# AFE_BQ-Chip.net
KiCad netlist of a schematic drawn in Altium Designer
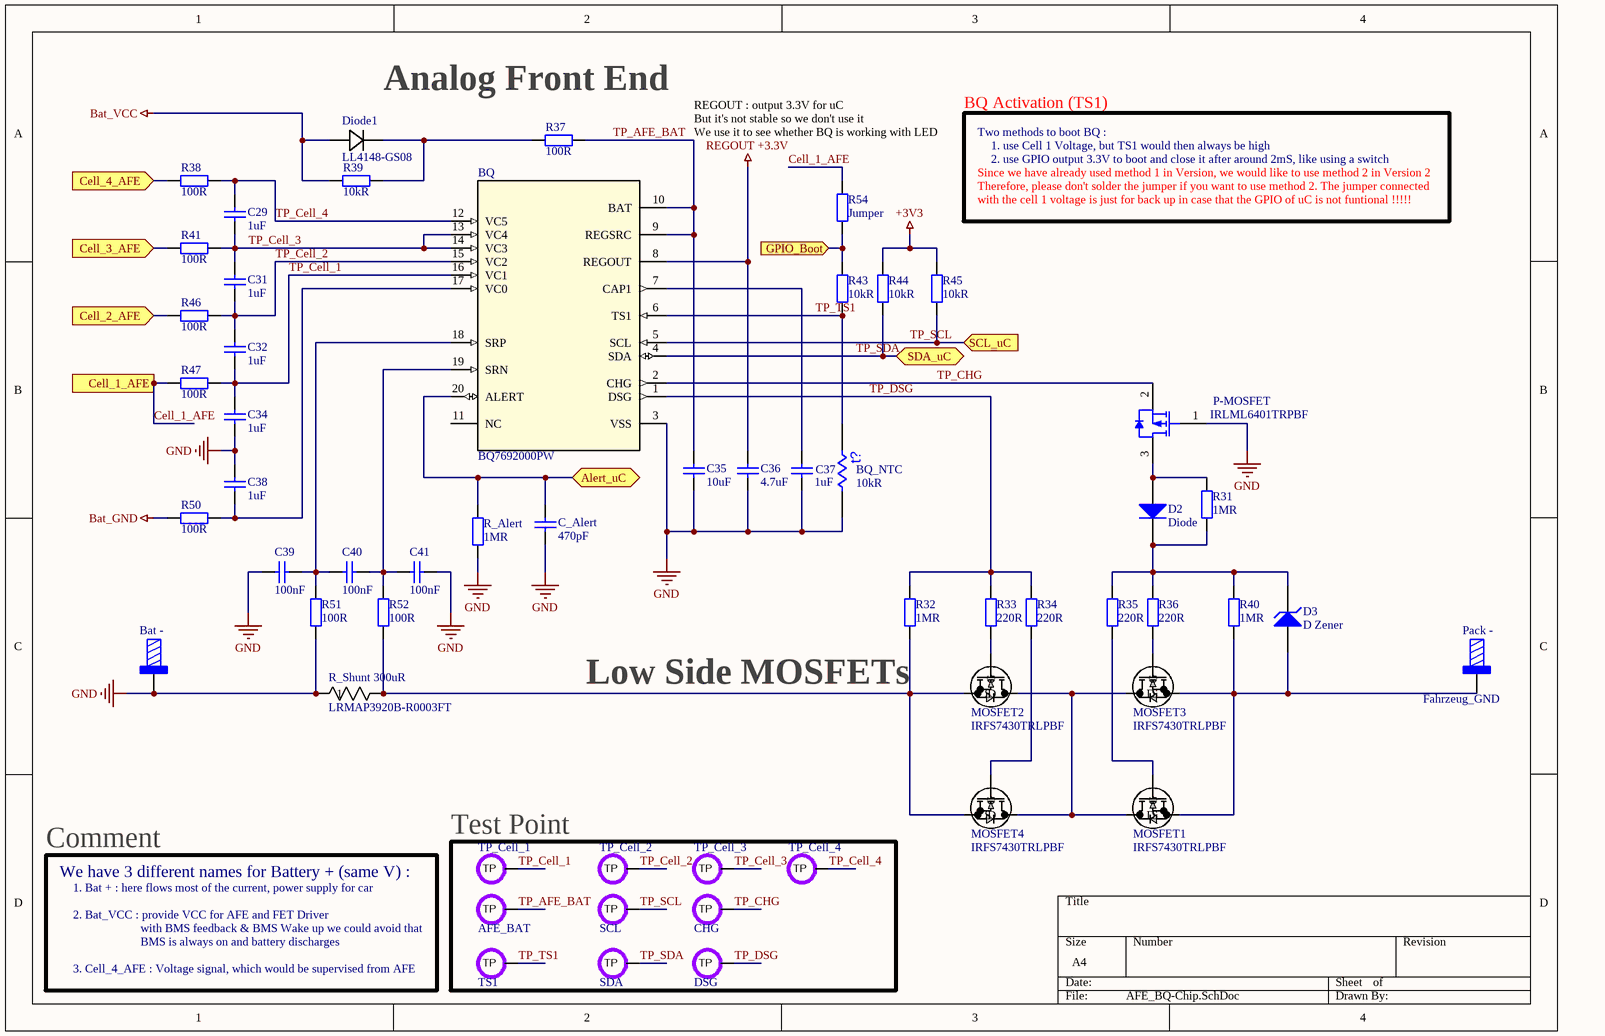
[diagram p0: AFE_BQ-Chip.SchDoc]

(export (version "E")
  (design (tool "Eeschema 10.0.6"))
  (components
    (comp (ref "AFE_BAT")
      (value "TP_1")
      (footprint "Test point")
      (libsource (lib "Schlib1") (part "Test point"))
    )
    (comp (ref "Bat -")
      (value "M4x6mm")
      (footprint "7461096_for chemical surfaces")
      (description "WP-SHFU Press-Fit with External thread, full plain, 7x7mm, 9 pins, M4x6mm, 130A")
      (fields (field (name "PART NUMBER") "7461096") (field (name "PUBLISHER") "Wurth Elektronik"))
      (libsource (lib "GND Pillar") (part "7461096"))
    )
    (comp (ref "BQ")
      (value "BQ7692000PW")
      (footprint "PW0020A_N")
      (description "AFE Cell battery monitor")
      (fields
        (field (name "PARTNUMBER") "BQ7692000PWR")
        (field (name "MANUFACTURER") "Texas Instruments")
        (field (name "COPYRIGHT") "Copyright (C) 2018 Accelerated Designs. All rights reserved")
      )
      (libsource (lib "BQ7692000PW") (part "BQ7692000PW"))
    )
    (comp (ref "BQ_NTC")
      (value "10kR")
      (footprint "J1-0603")
      (description "Thermistor")
      (fields (field (name "PUBLISHER") "Altium Limited"))
      (libsource (lib "Miscellaneous Devices") (part "Res Thermal"))
    )
    (comp (ref "C29")
      (value "1uF")
      (footprint "1608[0603]")
      (description "Capacitor")
      (fields (field (name "PUBLISHER") "Altium Limited"))
      (libsource (lib "Miscellaneous Devices") (part "Cap"))
    )
    (comp (ref "C31")
      (value "1uF")
      (footprint "1608[0603]")
      (description "Capacitor")
      (fields (field (name "PUBLISHER") "Altium Limited"))
      (libsource (lib "Miscellaneous Devices") (part "Cap"))
    )
    (comp (ref "C32")
      (value "1uF")
      (footprint "1608[0603]")
      (description "Capacitor")
      (fields (field (name "PUBLISHER") "Altium Limited"))
      (libsource (lib "Miscellaneous Devices") (part "Cap"))
    )
    (comp (ref "C34")
      (value "1uF")
      (footprint "1608[0603]")
      (description "Capacitor")
      (fields (field (name "PUBLISHER") "Altium Limited"))
      (libsource (lib "Miscellaneous Devices") (part "Cap"))
    )
    (comp (ref "C35")
      (value "10uF")
      (footprint "1608[0603]")
      (description "Capacitor")
      (fields (field (name "PUBLISHER") "Altium Limited"))
      (libsource (lib "Miscellaneous Devices") (part "Cap"))
    )
    (comp (ref "C36")
      (value "4.7uF")
      (footprint "1608[0603]")
      (description "Capacitor")
      (fields (field (name "PUBLISHER") "Altium Limited"))
      (libsource (lib "Miscellaneous Devices") (part "Cap"))
    )
    (comp (ref "C37")
      (value "1uF")
      (footprint "1608[0603]")
      (description "Capacitor")
      (fields (field (name "PUBLISHER") "Altium Limited"))
      (libsource (lib "Miscellaneous Devices") (part "Cap"))
    )
    (comp (ref "C38")
      (value "1uF")
      (footprint "1608[0603]")
      (description "Capacitor")
      (fields (field (name "PUBLISHER") "Altium Limited"))
      (libsource (lib "Miscellaneous Devices") (part "Cap"))
    )
    (comp (ref "C39")
      (value "100nF")
      (footprint "1608[0603]")
      (description "Capacitor")
      (fields (field (name "PUBLISHER") "Altium Limited"))
      (libsource (lib "Miscellaneous Devices") (part "Cap"))
    )
    (comp (ref "C40")
      (value "100nF")
      (footprint "1608[0603]")
      (description "Capacitor")
      (fields (field (name "PUBLISHER") "Altium Limited"))
      (libsource (lib "Miscellaneous Devices") (part "Cap"))
    )
    (comp (ref "C41")
      (value "100nF")
      (footprint "1608[0603]")
      (description "Capacitor")
      (fields (field (name "PUBLISHER") "Altium Limited"))
      (libsource (lib "Miscellaneous Devices") (part "Cap"))
    )
    (comp (ref "CHG") (value "TP_1") (footprint "Test point") (libsource (lib "Schlib1") (part "Test point")))
    (comp (ref "C_Alert")
      (value "470pF")
      (footprint "1608[0603]")
      (description "Capacitor")
      (fields (field (name "PUBLISHER") "Altium Limited"))
      (libsource (lib "Miscellaneous Devices") (part "Cap"))
    )
    (comp (ref "D2")
      (value "Diode")
      (footprint "SMB")
      (description "Default Diode")
      (fields (field (name "PUBLISHER") "Altium Limited"))
      (libsource (lib "Miscellaneous Devices") (part "Diode"))
    )
    (comp (ref "D3")
      (value "D Zener")
      (footprint "SMB")
      (description "Zener Diode")
      (fields (field (name "PUBLISHER") "Altium Limited"))
      (libsource (lib "Miscellaneous Devices") (part "D Zener"))
    )
    (comp (ref "Diode1")
      (value "LL4148-GS08")
      (footprint "MELF_SOD-80_VIS")
      (description "No Description Available")
      (fields (field (name "COPYRIGHT") "Copyright (C) 2018 Accelerated Designs. All rights reserved"))
      (libsource (lib "Small Signal Switching Diodes") (part "LL4148-GS08"))
    )
    (comp (ref "DSG") (value "TP_1") (footprint "Test point") (libsource (lib "Schlib1") (part "Test point")))
    (comp (ref "MOSFET1")
      (value "IRFS7430TRLPBF")
      (footprint "D2PAK_TO-263AB_INF-M")
      (description "No Description Available")
      (fields (field (name "COPYRIGHT") "Copyright (C) 2018 Accelerated Designs. All rights reserved"))
      (libsource (lib "Power MOSFET") (part "IRFS7430TRLPBF"))
    )
    (comp (ref "MOSFET2")
      (value "IRFS7430TRLPBF")
      (footprint "D2PAK_TO-263AB_INF-M")
      (description "No Description Available")
      (fields (field (name "COPYRIGHT") "Copyright (C) 2018 Accelerated Designs. All rights reserved"))
      (libsource (lib "Power MOSFET") (part "IRFS7430TRLPBF"))
    )
    (comp (ref "MOSFET3")
      (value "IRFS7430TRLPBF")
      (footprint "D2PAK_TO-263AB_INF-M")
      (description "No Description Available")
      (fields (field (name "COPYRIGHT") "Copyright (C) 2018 Accelerated Designs. All rights reserved"))
      (libsource (lib "Power MOSFET") (part "IRFS7430TRLPBF"))
    )
    (comp (ref "MOSFET4")
      (value "IRFS7430TRLPBF")
      (footprint "D2PAK_TO-263AB_INF-M")
      (description "No Description Available")
      (fields (field (name "COPYRIGHT") "Copyright (C) 2018 Accelerated Designs. All rights reserved"))
      (libsource (lib "Power MOSFET") (part "IRFS7430TRLPBF"))
    )
    (comp (ref "P-MOSFET")
      (value "IRLML6401TRPBF")
      (footprint "INTR-SOT-23-3_V")
      (fields (field (name "MANUFACTURER") "International Rectifier"))
      (libsource (lib "Altium Content Vault") (part "PEMOS-GSD-3"))
    )
    (comp (ref "Pack -")
      (value "Fahrzeug_GND")
      (footprint "7461096_for chemical surfaces")
      (description "WP-SHFU Press-Fit with External thread, full plain, 7x7mm, 9 pins, M4x6mm, 130A")
      (fields (field (name "PART NUMBER") "7461096") (field (name "PUBLISHER") "Wurth Elektronik"))
      (libsource (lib "GND Pillar") (part "7461096"))
    )
    (comp (ref "R31")
      (value "1MR")
      (footprint "J1-0603")
      (description "Resistor")
      (fields (field (name "PUBLISHER") "Altium Limited"))
      (libsource (lib "") (part "Res2_1"))
    )
    (comp (ref "R32")
      (value "1MR")
      (footprint "J1-0603")
      (description "Resistor")
      (fields (field (name "PUBLISHER") "Altium Limited"))
      (libsource (lib "") (part "Res2_1"))
    )
    (comp (ref "R33")
      (value "220R")
      (footprint "J1-0603")
      (description "Resistor")
      (fields (field (name "PUBLISHER") "Altium Limited"))
      (libsource (lib "") (part "Res2_1"))
    )
    (comp (ref "R34")
      (value "220R")
      (footprint "J1-0603")
      (description "Resistor")
      (fields (field (name "PUBLISHER") "Altium Limited"))
      (libsource (lib "") (part "Res2_1"))
    )
    (comp (ref "R35")
      (value "220R")
      (footprint "J1-0603")
      (description "Resistor")
      (fields (field (name "PUBLISHER") "Altium Limited"))
      (libsource (lib "") (part "Res2_1"))
    )
    (comp (ref "R36")
      (value "220R")
      (footprint "J1-0603")
      (description "Resistor")
      (fields (field (name "PUBLISHER") "Altium Limited"))
      (libsource (lib "") (part "Res2_1"))
    )
    (comp (ref "R37")
      (value "100R")
      (footprint "J1-0603")
      (description "Resistor")
      (fields (field (name "PUBLISHER") "Altium Limited"))
      (libsource (lib "Miscellaneous Devices") (part "Res2"))
    )
    (comp (ref "R38")
      (value "100R")
      (footprint "J1-0603")
      (description "Resistor")
      (fields (field (name "PUBLISHER") "Altium Limited"))
      (libsource (lib "Miscellaneous Devices") (part "Res2"))
    )
    (comp (ref "R39")
      (value "10kR")
      (footprint "J1-0603")
      (description "Resistor")
      (fields (field (name "PUBLISHER") "Altium Limited"))
      (libsource (lib "Miscellaneous Devices") (part "Res2"))
    )
    (comp (ref "R40")
      (value "1MR")
      (footprint "J1-0603")
      (description "Resistor")
      (fields (field (name "PUBLISHER") "Altium Limited"))
      (libsource (lib "") (part "Res2_1"))
    )
    (comp (ref "R41")
      (value "100R")
      (footprint "J1-0603")
      (description "Resistor")
      (fields (field (name "PUBLISHER") "Altium Limited"))
      (libsource (lib "Miscellaneous Devices") (part "Res2"))
    )
    (comp (ref "R43")
      (value "10kR")
      (footprint "J1-0603")
      (description "Resistor")
      (fields (field (name "PUBLISHER") "Altium Limited"))
      (libsource (lib "Miscellaneous Devices") (part "Res2"))
    )
    (comp (ref "R44")
      (value "10kR")
      (footprint "J1-0603")
      (description "Resistor")
      (fields (field (name "PUBLISHER") "Altium Limited"))
      (libsource (lib "") (part "Res2_1"))
    )
    (comp (ref "R45")
      (value "10kR")
      (footprint "J1-0603")
      (description "Resistor")
      (fields (field (name "PUBLISHER") "Altium Limited"))
      (libsource (lib "") (part "Res2_1"))
    )
    (comp (ref "R46")
      (value "100R")
      (footprint "J1-0603")
      (description "Resistor")
      (fields (field (name "PUBLISHER") "Altium Limited"))
      (libsource (lib "Miscellaneous Devices") (part "Res2"))
    )
    (comp (ref "R47")
      (value "100R")
      (footprint "J1-0603")
      (description "Resistor")
      (fields (field (name "PUBLISHER") "Altium Limited"))
      (libsource (lib "Miscellaneous Devices") (part "Res2"))
    )
    (comp (ref "R50")
      (value "100R")
      (footprint "J1-0603")
      (description "Resistor")
      (fields (field (name "PUBLISHER") "Altium Limited"))
      (libsource (lib "") (part "Res2_1"))
    )
    (comp (ref "R51")
      (value "100R")
      (footprint "J1-0603")
      (description "Resistor")
      (fields (field (name "PUBLISHER") "Altium Limited"))
      (libsource (lib "Miscellaneous Devices") (part "Res2"))
    )
    (comp (ref "R52")
      (value "100R")
      (footprint "J1-0603")
      (description "Resistor")
      (fields (field (name "PUBLISHER") "Altium Limited"))
      (libsource (lib "Miscellaneous Devices") (part "Res2"))
    )
    (comp (ref "R54")
      (value "Jumper")
      (footprint "J1-0603")
      (description "Resistor")
      (fields (field (name "PUBLISHER") "Altium Limited"))
      (libsource (lib "") (part "Res2_2"))
    )
    (comp (ref "R_Alert")
      (value "1MR")
      (footprint "J1-0603")
      (description "Resistor")
      (fields (field (name "PUBLISHER") "Altium Limited"))
      (libsource (lib "Miscellaneous Devices") (part "Res2"))
    )
    (comp (ref "R_Shunt 300uR")
      (value "LRMAP3920B-R0003FT")
      (footprint "RES_LRMAP3920B-R0003FT_WEL")
      (description "No Description Available")
      (fields (field (name "COPYRIGHT") "Copyright (C) 2018 Accelerated Designs. All rights reserved"))
      (libsource (lib "Shunt R") (part "LRMAP3920B-R0003FT"))
    )
    (comp (ref "SCL") (value "TP_1") (footprint "Test point") (libsource (lib "Schlib1") (part "Test point")))
    (comp (ref "SDA") (value "TP_1") (footprint "Test point") (libsource (lib "Schlib1") (part "Test point")))
    (comp (ref "TP_Cell_1")
      (value "TP_1")
      (footprint "Test point")
      (libsource (lib "Schlib1") (part "Test point"))
    )
    (comp (ref "TP_Cell_2")
      (value "TP_1")
      (footprint "Test point")
      (libsource (lib "Schlib1") (part "Test point"))
    )
    (comp (ref "TP_Cell_3")
      (value "TP_1")
      (footprint "Test point")
      (libsource (lib "Schlib1") (part "Test point"))
    )
    (comp (ref "TP_Cell_4")
      (value "TP_1")
      (footprint "Test point")
      (libsource (lib "Schlib1") (part "Test point"))
    )
    (comp (ref "TS1") (value "TP_1") (footprint "Test point") (libsource (lib "Schlib1") (part "Test point")))
  )
  (nets
    (net (code "1") (name "+3V3") (class "Default")
      (node (ref "R44") (pin "1") (pinfunction "1_1") (pintype "passive"))
      (node (ref "R45") (pin "1") (pinfunction "1_1") (pintype "passive"))
    )
    (net (code "2") (name "/Alert_uC") (class "Default")
      (node (ref "BQ") (pin "20") (pinfunction "ALERT_20") (pintype "bidirectional"))
      (node (ref "C_Alert") (pin "1") (pinfunction "1_1") (pintype "passive"))
      (node (ref "R_Alert") (pin "1") (pinfunction "1_1") (pintype "passive"))
    )
    (net (code "3") (name "/Cell_1_AFE") (class "Default")
      (node (ref "R47") (pin "2") (pinfunction "2_2") (pintype "passive"))
      (node (ref "R54") (pin "2") (pinfunction "2_2") (pintype "passive"))
    )
    (net (code "4") (name "/Cell_2_AFE") (class "Default")
      (node (ref "R46") (pin "2") (pinfunction "2_2") (pintype "passive"))
    )
    (net (code "5") (name "/Cell_3_AFE") (class "Default")
      (node (ref "R41") (pin "2") (pinfunction "2_2") (pintype "passive"))
    )
    (net (code "6") (name "/Cell_4_AFE") (class "Default")
      (node (ref "R38") (pin "2") (pinfunction "2_2") (pintype "passive"))
    )
    (net (code "7") (name "/GPIO_Boot") (class "Default")
      (node (ref "R43") (pin "1") (pinfunction "1_1") (pintype "passive"))
      (node (ref "R54") (pin "1") (pinfunction "1_1") (pintype "passive"))
    )
    (net (code "8") (name "/TP_AFE_BAT") (class "Default")
      (node (ref "AFE_BAT") (pin "1") (pinfunction "TP_1") (pintype "passive"))
      (node (ref "BQ") (pin "10") (pinfunction "BAT_10") (pintype "power_in"))
      (node (ref "BQ") (pin "9") (pinfunction "REGSRC_9") (pintype "power_in"))
      (node (ref "C35") (pin "1") (pinfunction "1_1") (pintype "passive"))
      (node (ref "R37") (pin "1") (pinfunction "1_1") (pintype "passive"))
    )
    (net (code "9") (name "/TP_CHG") (class "Default")
      (node (ref "BQ") (pin "2") (pinfunction "CHG_2") (pintype "output"))
      (node (ref "CHG") (pin "1") (pinfunction "TP_1") (pintype "passive"))
      (node (ref "P-MOSFET") (pin "2") (pinfunction "SOURCE_2") (pintype "passive"))
    )
    (net (code "10") (name "/TP_Cell_1") (class "Default")
      (node (ref "BQ") (pin "16") (pinfunction "VC1_16") (pintype "input"))
      (node (ref "C32") (pin "1") (pinfunction "1_1") (pintype "passive"))
      (node (ref "C34") (pin "2") (pinfunction "2_2") (pintype "passive"))
      (node (ref "R47") (pin "1") (pinfunction "1_1") (pintype "passive"))
      (node (ref "TP_Cell_1") (pin "1") (pinfunction "TP_1") (pintype "passive"))
    )
    (net (code "11") (name "/TP_Cell_2") (class "Default")
      (node (ref "BQ") (pin "15") (pinfunction "VC2_15") (pintype "input"))
      (node (ref "C31") (pin "1") (pinfunction "1_1") (pintype "passive"))
      (node (ref "C32") (pin "2") (pinfunction "2_2") (pintype "passive"))
      (node (ref "R46") (pin "1") (pinfunction "1_1") (pintype "passive"))
      (node (ref "TP_Cell_2") (pin "1") (pinfunction "TP_1") (pintype "passive"))
    )
    (net (code "12") (name "/TP_Cell_3") (class "Default")
      (node (ref "BQ") (pin "13") (pinfunction "VC4_13") (pintype "input"))
      (node (ref "BQ") (pin "14") (pinfunction "VC3_14") (pintype "input"))
      (node (ref "C29") (pin "1") (pinfunction "1_1") (pintype "passive"))
      (node (ref "C31") (pin "2") (pinfunction "2_2") (pintype "passive"))
      (node (ref "R41") (pin "1") (pinfunction "1_1") (pintype "passive"))
      (node (ref "TP_Cell_3") (pin "1") (pinfunction "TP_1") (pintype "passive"))
    )
    (net (code "13") (name "/TP_Cell_4") (class "Default")
      (node (ref "BQ") (pin "12") (pinfunction "VC5_12") (pintype "input"))
      (node (ref "C29") (pin "2") (pinfunction "2_2") (pintype "passive"))
      (node (ref "R38") (pin "1") (pinfunction "1_1") (pintype "passive"))
      (node (ref "TP_Cell_4") (pin "1") (pinfunction "TP_1") (pintype "passive"))
    )
    (net (code "14") (name "/TP_DSG") (class "Default")
      (node (ref "BQ") (pin "1") (pinfunction "DSG_1") (pintype "output"))
      (node (ref "DSG") (pin "1") (pinfunction "TP_1") (pintype "passive"))
      (node (ref "R32") (pin "1") (pinfunction "1_1") (pintype "passive"))
      (node (ref "R33") (pin "1") (pinfunction "1_1") (pintype "passive"))
      (node (ref "R34") (pin "1") (pinfunction "1_1") (pintype "passive"))
    )
    (net (code "15") (name "/TP_SCL") (class "Default")
      (node (ref "BQ") (pin "5") (pinfunction "SCL_5") (pintype "input"))
      (node (ref "R45") (pin "2") (pinfunction "2_2") (pintype "passive"))
      (node (ref "SCL") (pin "1") (pinfunction "TP_1") (pintype "passive"))
    )
    (net (code "16") (name "/TP_SDA") (class "Default")
      (node (ref "BQ") (pin "4") (pinfunction "SDA_4") (pintype "bidirectional"))
      (node (ref "R44") (pin "2") (pinfunction "2_2") (pintype "passive"))
      (node (ref "SDA") (pin "1") (pinfunction "TP_1") (pintype "passive"))
    )
    (net (code "17") (name "/TP_TS1") (class "Default")
      (node (ref "BQ") (pin "6") (pinfunction "TS1_6") (pintype "input"))
      (node (ref "BQ_NTC") (pin "1") (pinfunction "1_1") (pintype "passive"))
      (node (ref "R43") (pin "2") (pinfunction "2_2") (pintype "passive"))
      (node (ref "TS1") (pin "1") (pinfunction "TP_1") (pintype "passive"))
    )
    (net (code "18") (name "Bat_GND") (class "Default")
      (node (ref "R50") (pin "2") (pinfunction "2_2") (pintype "passive"))
    )
    (net (code "19") (name "Bat_VCC") (class "Default")
      (node (ref "Diode1") (pin "2") (pinfunction "2_2") (pintype "passive"))
      (node (ref "R39") (pin "2") (pinfunction "2_2") (pintype "passive"))
    )
    (net (code "20") (name "GND") (class "Default")
      (node (ref "BQ") (pin "3") (pinfunction "VSS_3") (pintype "power_in"))
      (node (ref "BQ_NTC") (pin "2") (pinfunction "2_2") (pintype "passive"))
      (node (ref "Bat -") (pin "1") (pinfunction "1_1") (pintype "passive"))
      (node (ref "C34") (pin "1") (pinfunction "1_1") (pintype "passive"))
      (node (ref "C35") (pin "2") (pinfunction "2_2") (pintype "passive"))
      (node (ref "C36") (pin "2") (pinfunction "2_2") (pintype "passive"))
      (node (ref "C37") (pin "2") (pinfunction "2_2") (pintype "passive"))
      (node (ref "C38") (pin "1") (pinfunction "1_1") (pintype "passive"))
      (node (ref "C39") (pin "2") (pinfunction "2_2") (pintype "passive"))
      (node (ref "C41") (pin "1") (pinfunction "1_1") (pintype "passive"))
      (node (ref "C_Alert") (pin "2") (pinfunction "2_2") (pintype "passive"))
      (node (ref "P-MOSFET") (pin "1") (pinfunction "GATE_1") (pintype "passive"))
      (node (ref "R51") (pin "2") (pinfunction "2_2") (pintype "passive"))
      (node (ref "R_Alert") (pin "2") (pinfunction "2_2") (pintype "passive"))
      (node (ref "R_Shunt 300uR") (pin "1") (pinfunction "1_1") (pintype "passive"))
    )
    (net (code "21") (name "Net-(BQ-CAP1)") (class "Default")
      (node (ref "BQ") (pin "7") (pinfunction "CAP1_7") (pintype "output"))
      (node (ref "C37") (pin "1") (pinfunction "1_1") (pintype "passive"))
    )
    (net (code "22") (name "Net-(BQ-SRN)") (class "Default")
      (node (ref "BQ") (pin "19") (pinfunction "SRN_19") (pintype "input"))
      (node (ref "C40") (pin "1") (pinfunction "1_1") (pintype "passive"))
      (node (ref "C41") (pin "2") (pinfunction "2_2") (pintype "passive"))
      (node (ref "R52") (pin "1") (pinfunction "1_1") (pintype "passive"))
    )
    (net (code "23") (name "Net-(BQ-SRP)") (class "Default")
      (node (ref "BQ") (pin "18") (pinfunction "SRP_18") (pintype "input"))
      (node (ref "C39") (pin "1") (pinfunction "1_1") (pintype "passive"))
      (node (ref "C40") (pin "2") (pinfunction "2_2") (pintype "passive"))
      (node (ref "R51") (pin "1") (pinfunction "1_1") (pintype "passive"))
    )
    (net (code "24") (name "Net-(BQ-VC0)") (class "Default")
      (node (ref "BQ") (pin "17") (pinfunction "VC0_17") (pintype "input"))
      (node (ref "C38") (pin "2") (pinfunction "2_2") (pintype "passive"))
      (node (ref "R50") (pin "1") (pinfunction "1_1") (pintype "passive"))
    )
    (net (code "25") (name "Net-(D2-A)") (class "Default")
      (node (ref "D2") (pin "1") (pinfunction "A_1") (pintype "passive"))
      (node (ref "P-MOSFET") (pin "3") (pinfunction "DRAIN_3") (pintype "passive"))
      (node (ref "R31") (pin "1") (pinfunction "1_1") (pintype "passive"))
    )
    (net (code "26") (name "Net-(D2-K)") (class "Default")
      (node (ref "D2") (pin "2") (pinfunction "K_2") (pintype "passive"))
      (node (ref "D3") (pin "2") (pinfunction "K_2") (pintype "passive"))
      (node (ref "R31") (pin "2") (pinfunction "2_2") (pintype "passive"))
      (node (ref "R35") (pin "1") (pinfunction "1_1") (pintype "passive"))
      (node (ref "R36") (pin "1") (pinfunction "1_1") (pintype "passive"))
      (node (ref "R40") (pin "1") (pinfunction "1_1") (pintype "passive"))
    )
    (net (code "27") (name "Net-(D3-A)") (class "Default")
      (node (ref "D3") (pin "1") (pinfunction "A_1") (pintype "passive"))
      (node (ref "MOSFET1") (pin "3") (pinfunction "S_3") (pintype "passive"))
      (node (ref "MOSFET3") (pin "3") (pinfunction "S_3") (pintype "passive"))
      (node (ref "Pack -") (pin "1") (pinfunction "1_1") (pintype "passive"))
      (node (ref "R40") (pin "2") (pinfunction "2_2") (pintype "passive"))
    )
    (net (code "28") (name "Net-(Diode1-Pad1)") (class "Default")
      (node (ref "Diode1") (pin "1") (pinfunction "1_1") (pintype "passive"))
      (node (ref "R37") (pin "2") (pinfunction "2_2") (pintype "passive"))
      (node (ref "R39") (pin "1") (pinfunction "1_1") (pintype "passive"))
    )
    (net (code "29") (name "Net-(MOSFET1-D)") (class "Default")
      (node (ref "MOSFET1") (pin "2") (pinfunction "D_2") (pintype "passive"))
      (node (ref "MOSFET2") (pin "2") (pinfunction "D_2") (pintype "passive"))
      (node (ref "MOSFET3") (pin "2") (pinfunction "D_2") (pintype "passive"))
      (node (ref "MOSFET4") (pin "2") (pinfunction "D_2") (pintype "passive"))
    )
    (net (code "30") (name "Net-(MOSFET1-G)") (class "Default")
      (node (ref "MOSFET1") (pin "1") (pinfunction "G_1") (pintype "passive"))
      (node (ref "R35") (pin "2") (pinfunction "2_2") (pintype "passive"))
    )
    (net (code "31") (name "Net-(MOSFET2-G)") (class "Default")
      (node (ref "MOSFET2") (pin "1") (pinfunction "G_1") (pintype "passive"))
      (node (ref "R33") (pin "2") (pinfunction "2_2") (pintype "passive"))
    )
    (net (code "32") (name "Net-(MOSFET2-S)") (class "Default")
      (node (ref "MOSFET2") (pin "3") (pinfunction "S_3") (pintype "passive"))
      (node (ref "MOSFET4") (pin "3") (pinfunction "S_3") (pintype "passive"))
      (node (ref "R32") (pin "2") (pinfunction "2_2") (pintype "passive"))
      (node (ref "R52") (pin "2") (pinfunction "2_2") (pintype "passive"))
      (node (ref "R_Shunt 300uR") (pin "2") (pinfunction "2_2") (pintype "passive"))
    )
    (net (code "33") (name "Net-(MOSFET3-G)") (class "Default")
      (node (ref "MOSFET3") (pin "1") (pinfunction "G_1") (pintype "passive"))
      (node (ref "R36") (pin "2") (pinfunction "2_2") (pintype "passive"))
    )
    (net (code "34") (name "Net-(MOSFET4-G)") (class "Default")
      (node (ref "MOSFET4") (pin "1") (pinfunction "G_1") (pintype "passive"))
      (node (ref "R34") (pin "2") (pinfunction "2_2") (pintype "passive"))
    )
    (net (code "35") (name "REGOUT +3.3V") (class "Default")
      (node (ref "BQ") (pin "8") (pinfunction "REGOUT_8") (pintype "power_in"))
      (node (ref "C36") (pin "1") (pinfunction "1_1") (pintype "passive"))
    )
    (net (code "36") (name "unconnected-(BQ-NC-Pad11)") (class "Default")
      (node (ref "BQ") (pin "11") (pinfunction "NC_11") (pintype "passive"))
    )
  )
)
